# Quimera_Power-distribution.net
KiCad netlist of a schematic drawn in EAGLE
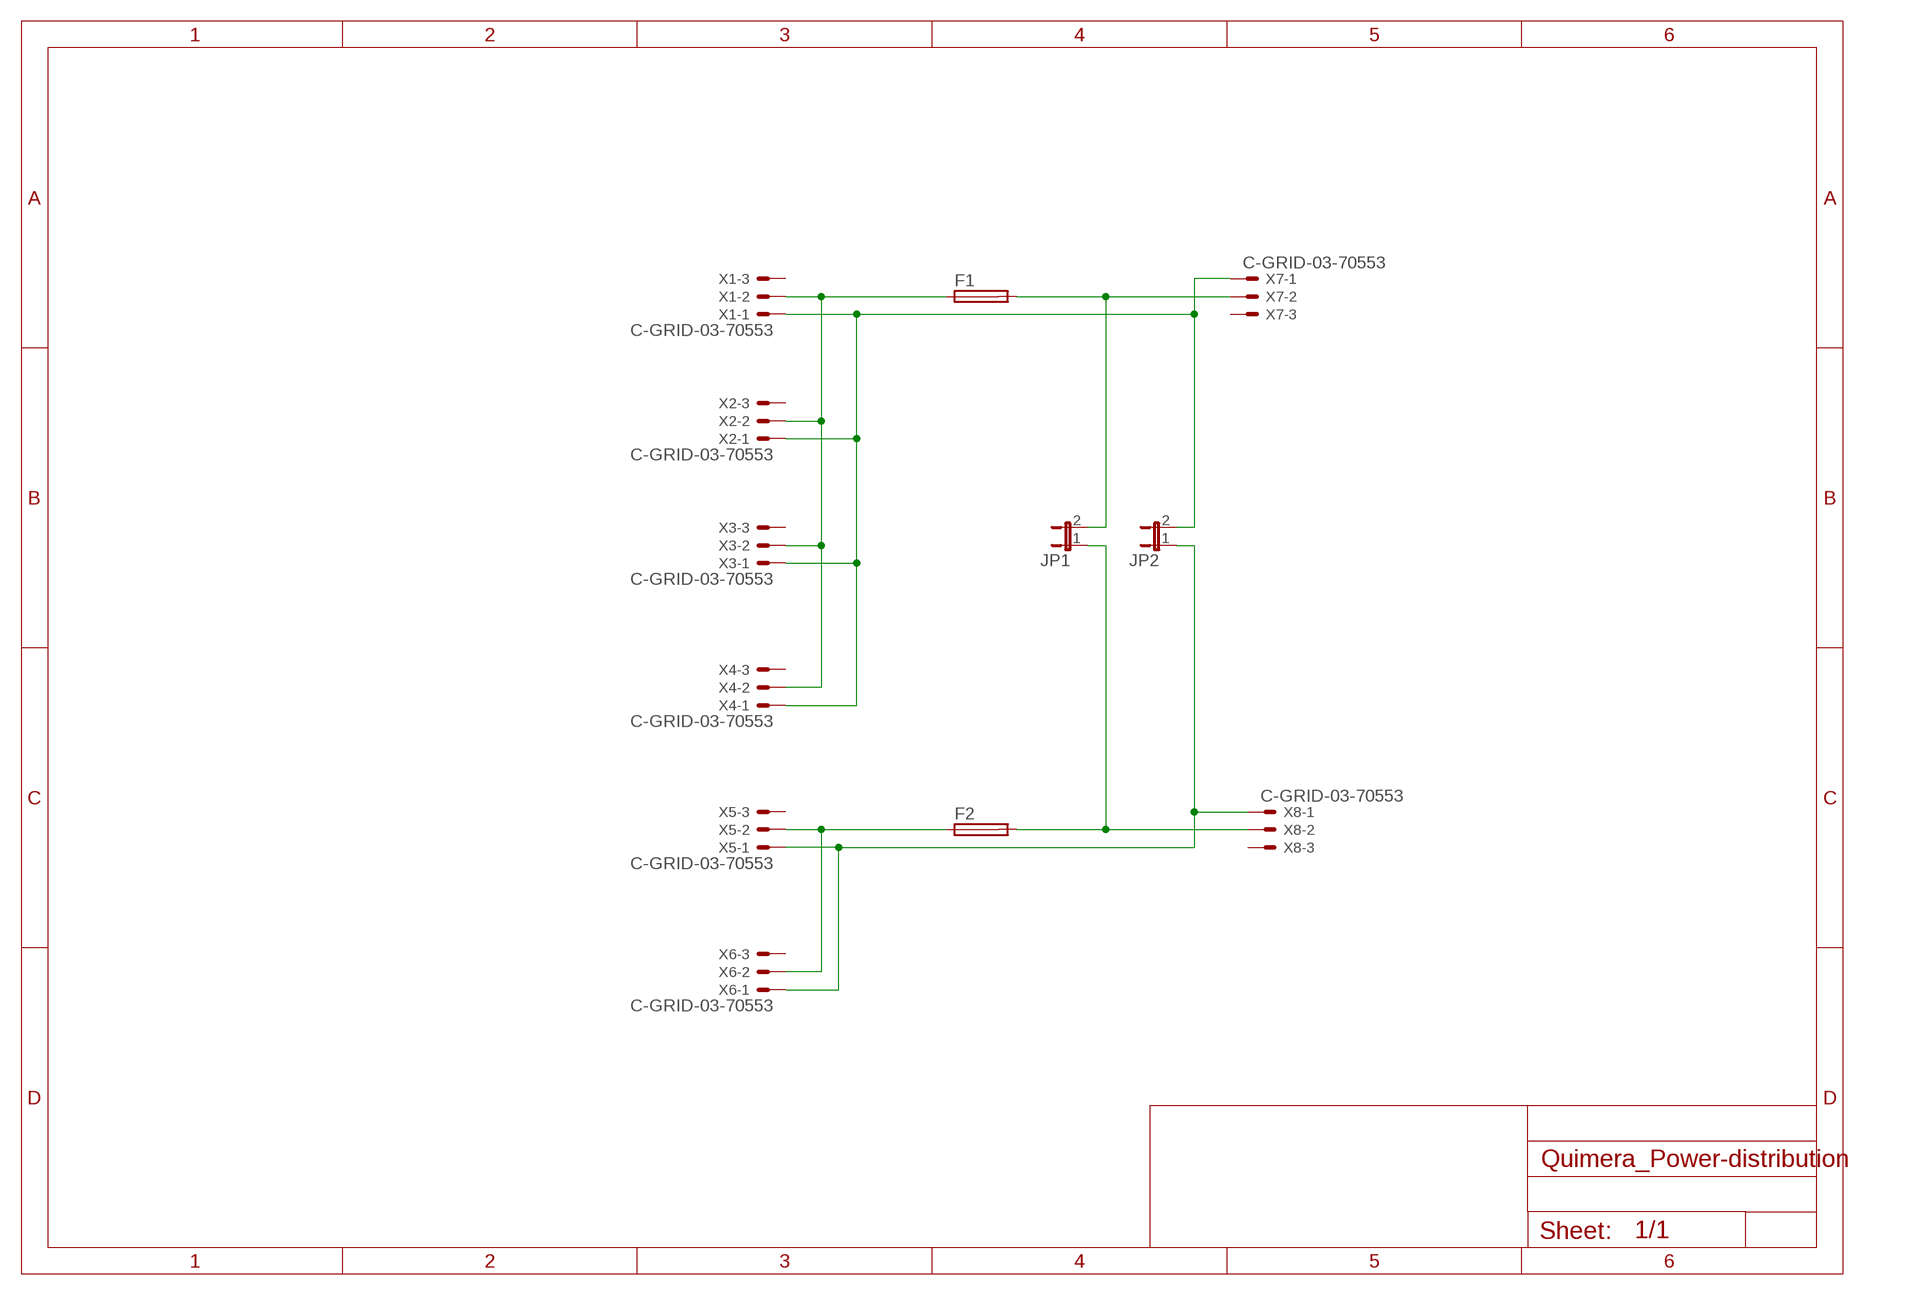
[diagram p0: schematic, sheet 1]

(export (version "E")
  (design (tool "Eeschema 10.0.6"))
  (components
    (comp (ref "F1")
      (value "SH22,5A")
      (footprint "eagle-import:SH22,5A")
      (fields (field (name "MPN") "0031.7701.11"))
      (libsource (lib "eagle-import") (part "SH22,5A"))
    )
    (comp (ref "F2")
      (value "SH22,5A")
      (footprint "eagle-import:SH22,5A")
      (fields (field (name "MPN") "0031.7701.11"))
      (libsource (lib "eagle-import") (part "SH22,5A"))
    )
    (comp (ref "JP1")
      (value "JP1E")
      (footprint "eagle-import:JP1")
      (libsource (lib "eagle-import") (part "JP1E"))
    )
    (comp (ref "JP2")
      (value "JP1E")
      (footprint "eagle-import:JP1")
      (libsource (lib "eagle-import") (part "JP1E"))
    )
    (comp (ref "X1")
      (value "C-GRID-03-70553")
      (footprint "eagle-import:70553-03")
      (libsource (lib "eagle-import") (part "C-GRID-03-70553"))
    )
    (comp (ref "X2")
      (value "C-GRID-03-70553")
      (footprint "eagle-import:70553-03")
      (libsource (lib "eagle-import") (part "C-GRID-03-70553"))
    )
    (comp (ref "X3")
      (value "C-GRID-03-70553")
      (footprint "eagle-import:70553-03")
      (libsource (lib "eagle-import") (part "C-GRID-03-70553"))
    )
    (comp (ref "X4")
      (value "C-GRID-03-70553")
      (footprint "eagle-import:70553-03")
      (libsource (lib "eagle-import") (part "C-GRID-03-70553"))
    )
    (comp (ref "X5")
      (value "C-GRID-03-70553")
      (footprint "eagle-import:70553-03")
      (libsource (lib "eagle-import") (part "C-GRID-03-70553"))
    )
    (comp (ref "X6")
      (value "C-GRID-03-70553")
      (footprint "eagle-import:70553-03")
      (libsource (lib "eagle-import") (part "C-GRID-03-70553"))
    )
    (comp (ref "X7")
      (value "C-GRID-03-70553")
      (footprint "eagle-import:70553-03")
      (libsource (lib "eagle-import") (part "C-GRID-03-70553"))
    )
    (comp (ref "X8")
      (value "C-GRID-03-70553")
      (footprint "eagle-import:70553-03")
      (libsource (lib "eagle-import") (part "C-GRID-03-70553"))
    )
  )
  (nets
    (net (code "1") (name "Net-(X1A-S)") (class "Default")
      (node (ref "JP2") (pin "2") (pinfunction "2_2") (pintype "passive"))
      (node (ref "X1") (pin "1") (pinfunction "S_1") (pintype "passive"))
      (node (ref "X2") (pin "1") (pinfunction "S_1") (pintype "passive"))
      (node (ref "X3") (pin "1") (pinfunction "S_1") (pintype "passive"))
      (node (ref "X4") (pin "1") (pinfunction "S_1") (pintype "passive"))
      (node (ref "X7") (pin "1") (pinfunction "S_1") (pintype "passive"))
    )
    (net (code "2") (name "Net-(X1B-S)") (class "Default")
      (node (ref "F1") (pin "1") (pinfunction "1_1") (pintype "passive"))
      (node (ref "X1") (pin "2") (pinfunction "S_2") (pintype "passive"))
      (node (ref "X2") (pin "2") (pinfunction "S_2") (pintype "passive"))
      (node (ref "X3") (pin "2") (pinfunction "S_2") (pintype "passive"))
      (node (ref "X4") (pin "2") (pinfunction "S_2") (pintype "passive"))
    )
    (net (code "3") (name "Net-(X5A-S)") (class "Default")
      (node (ref "JP2") (pin "1") (pinfunction "1_1") (pintype "passive"))
      (node (ref "X5") (pin "1") (pinfunction "S_1") (pintype "passive"))
      (node (ref "X6") (pin "1") (pinfunction "S_1") (pintype "passive"))
      (node (ref "X8") (pin "1") (pinfunction "S_1") (pintype "passive"))
    )
    (net (code "4") (name "Net-(X5B-S)") (class "Default")
      (node (ref "F2") (pin "1") (pinfunction "1_1") (pintype "passive"))
      (node (ref "X5") (pin "2") (pinfunction "S_2") (pintype "passive"))
      (node (ref "X6") (pin "2") (pinfunction "S_2") (pintype "passive"))
    )
    (net (code "5") (name "Net-(X7B-S)") (class "Default")
      (node (ref "F1") (pin "2") (pinfunction "2_2") (pintype "passive"))
      (node (ref "JP1") (pin "2") (pinfunction "2_2") (pintype "passive"))
      (node (ref "X7") (pin "2") (pinfunction "S_2") (pintype "passive"))
    )
    (net (code "6") (name "Net-(X8B-S)") (class "Default")
      (node (ref "F2") (pin "2") (pinfunction "2_2") (pintype "passive"))
      (node (ref "JP1") (pin "1") (pinfunction "1_1") (pintype "passive"))
      (node (ref "X8") (pin "2") (pinfunction "S_2") (pintype "passive"))
    )
    (net (code "7") (name "unconnected-(X1C-S-Pad3)") (class "Default")
      (node (ref "X1") (pin "3") (pinfunction "S_3") (pintype "passive"))
    )
    (net (code "8") (name "unconnected-(X2C-S-Pad3)") (class "Default")
      (node (ref "X2") (pin "3") (pinfunction "S_3") (pintype "passive"))
    )
    (net (code "9") (name "unconnected-(X3C-S-Pad3)") (class "Default")
      (node (ref "X3") (pin "3") (pinfunction "S_3") (pintype "passive"))
    )
    (net (code "10") (name "unconnected-(X4C-S-Pad3)") (class "Default")
      (node (ref "X4") (pin "3") (pinfunction "S_3") (pintype "passive"))
    )
    (net (code "11") (name "unconnected-(X5C-S-Pad3)") (class "Default")
      (node (ref "X5") (pin "3") (pinfunction "S_3") (pintype "passive"))
    )
    (net (code "12") (name "unconnected-(X6C-S-Pad3)") (class "Default")
      (node (ref "X6") (pin "3") (pinfunction "S_3") (pintype "passive"))
    )
    (net (code "13") (name "unconnected-(X7C-S-Pad3)") (class "Default")
      (node (ref "X7") (pin "3") (pinfunction "S_3") (pintype "passive"))
    )
    (net (code "14") (name "unconnected-(X8C-S-Pad3)") (class "Default")
      (node (ref "X8") (pin "3") (pinfunction "S_3") (pintype "passive"))
    )
  )
)
